# Schematic.net
KiCad netlist of a schematic drawn in EAGLE
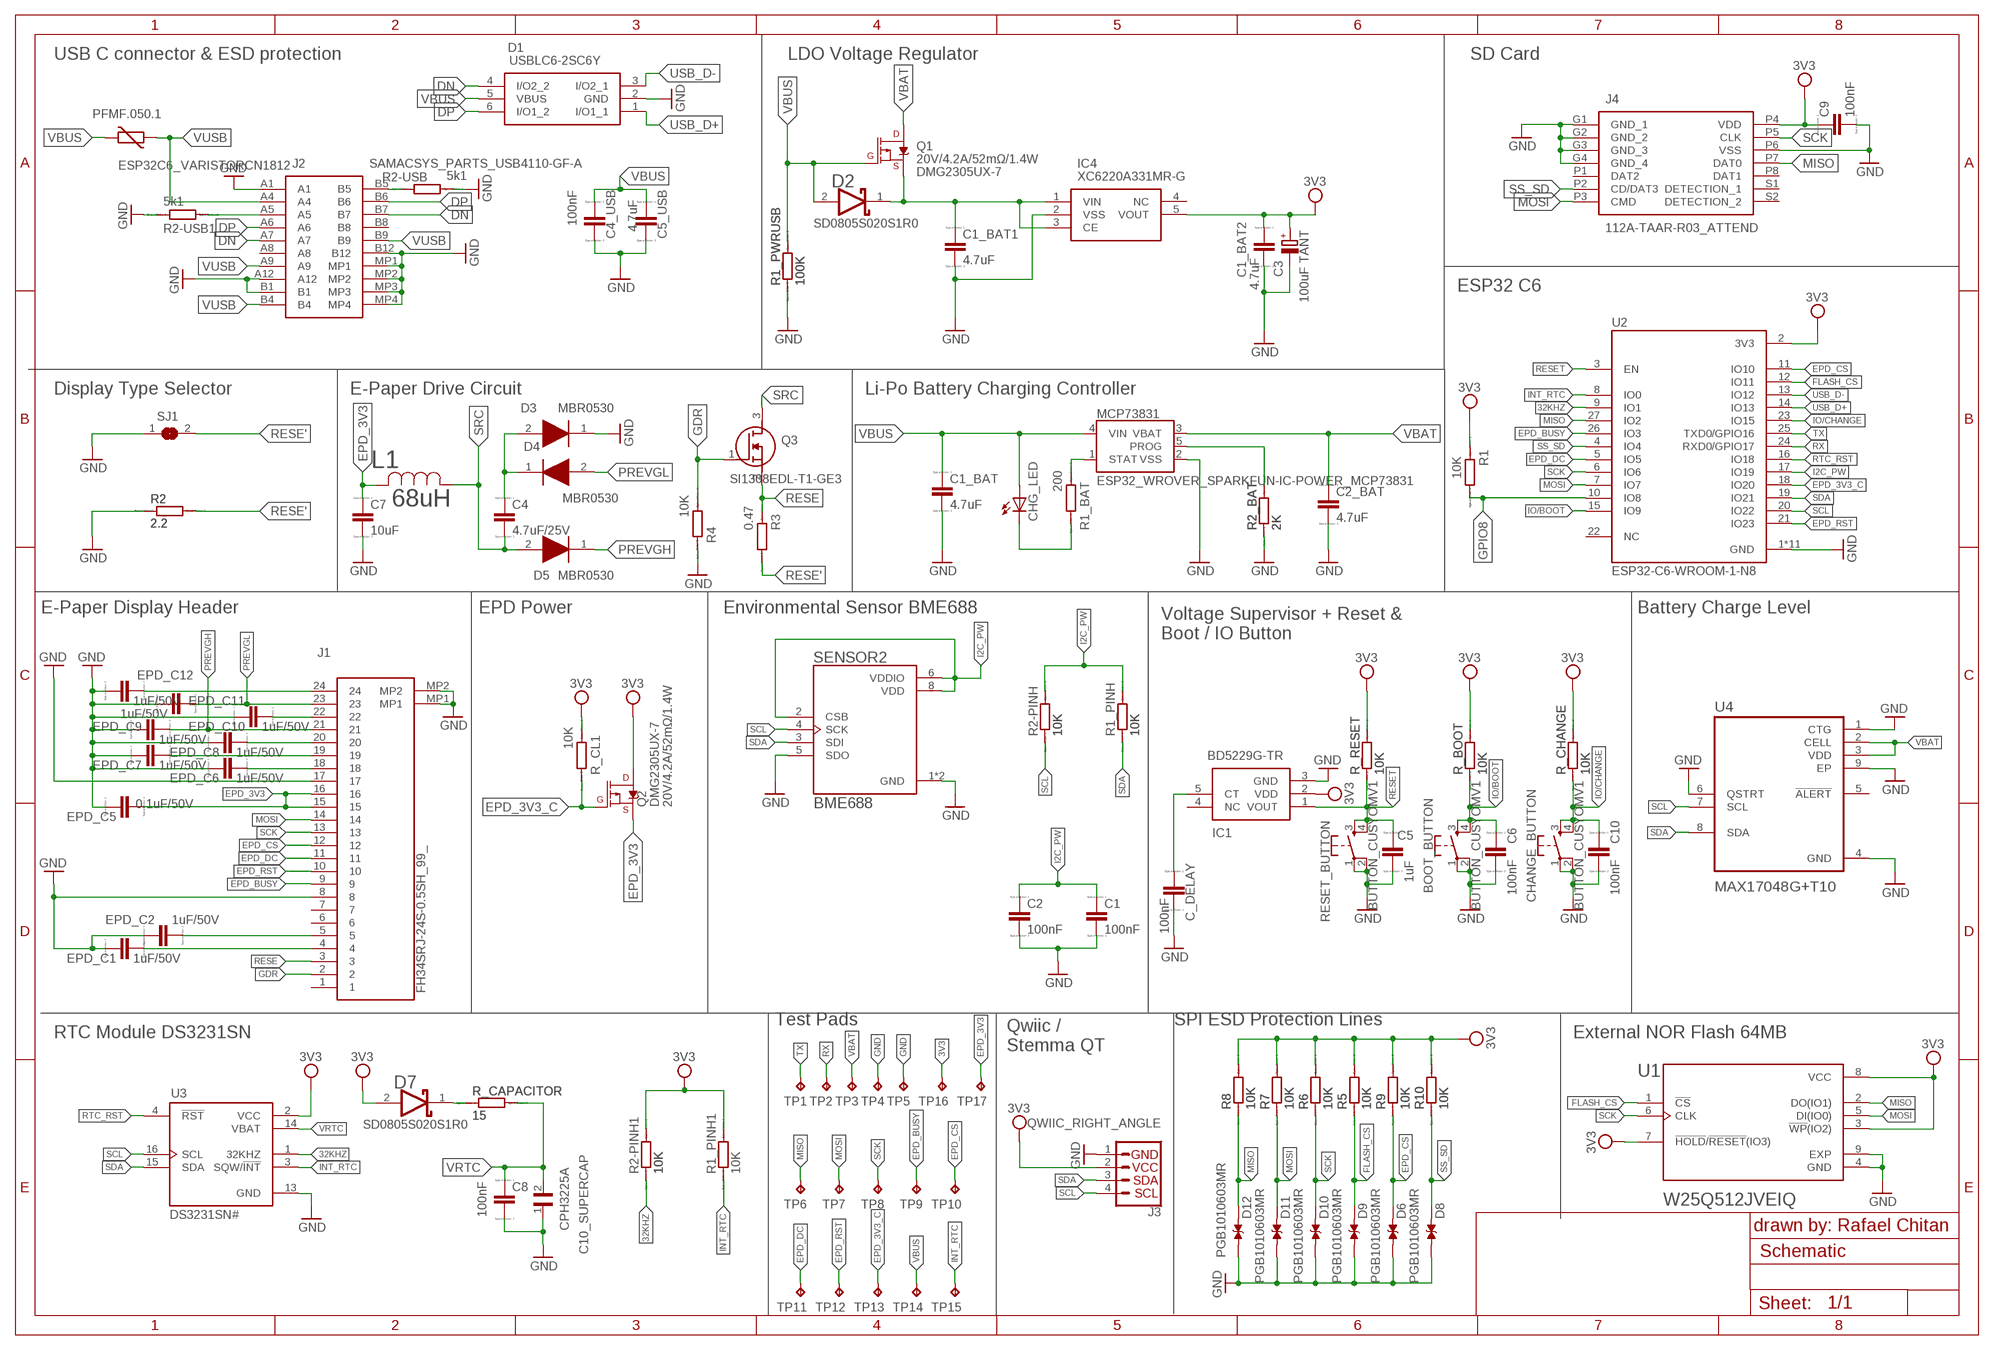
[diagram p0: schematic, sheet 1]

(export (version "E")
  (design (tool "Eeschema 10.0.6"))
  (components
    (comp (ref "BOOT_BUTTON")
      (value "BUTTON_CUSYOMV1")
      (footprint "eagle-import:MYBUTTON")
      (libsource (lib "eagle-import") (part "BUTTON_CUSYOMV1"))
    )
    (comp (ref "C1")
      (value "100nF")
      (footprint "eagle-import:EAGLE-LTSPICE_C0402")
      (libsource (lib "eagle-import") (part "EAGLE-LTSPICE_CC0402"))
    )
    (comp (ref "C1_BAT")
      (value "4.7uF")
      (footprint "eagle-import:EAGLE-LTSPICE_C0402")
      (libsource (lib "eagle-import") (part "EAGLE-LTSPICE_CC0402"))
    )
    (comp (ref "C1_BAT1")
      (value "4.7uF")
      (footprint "eagle-import:EAGLE-LTSPICE_C0402")
      (libsource (lib "eagle-import") (part "ESP32_WROVER_EAGLE-LTSPICE_CC0402"))
    )
    (comp (ref "C1_BAT2")
      (value "4.7uF")
      (footprint "eagle-import:EAGLE-LTSPICE_C0402")
      (libsource (lib "eagle-import") (part "ESP32_WROVER_EAGLE-LTSPICE_CC0402"))
    )
    (comp (ref "C2")
      (value "100nF")
      (footprint "eagle-import:EAGLE-LTSPICE_C0402")
      (libsource (lib "eagle-import") (part "EAGLE-LTSPICE_CC0402"))
    )
    (comp (ref "C2_BAT")
      (value "4.7uF")
      (footprint "eagle-import:EAGLE-LTSPICE_C0402")
      (libsource (lib "eagle-import") (part "EAGLE-LTSPICE_CC0402"))
    )
    (comp (ref "C3")
      (value "100uF TANT")
      (footprint "eagle-import:RCL_CT3528")
      (libsource (lib "eagle-import") (part "RCL_CPOL-EUCT3528"))
    )
    (comp (ref "C4")
      (value "4.7uF/25V")
      (footprint "eagle-import:EAGLE-LTSPICE_C0402")
      (libsource (lib "eagle-import") (part "EAGLE-LTSPICE_CC0402"))
    )
    (comp (ref "C4_USB")
      (value "100nF")
      (footprint "eagle-import:EAGLE-LTSPICE_C0402")
      (libsource (lib "eagle-import") (part "ESP32_WROVER_EAGLE-LTSPICE_CC0402"))
    )
    (comp (ref "C5")
      (value "1uF")
      (footprint "eagle-import:EAGLE-LTSPICE_C0402")
      (libsource (lib "eagle-import") (part "EAGLE-LTSPICE_CC0402"))
    )
    (comp (ref "C5_USB")
      (value "4.7uF")
      (footprint "eagle-import:EAGLE-LTSPICE_C0402")
      (libsource (lib "eagle-import") (part "ESP32_WROVER_EAGLE-LTSPICE_CC0402"))
    )
    (comp (ref "C6")
      (value "100nF")
      (footprint "eagle-import:EAGLE-LTSPICE_C0402")
      (libsource (lib "eagle-import") (part "EAGLE-LTSPICE_CC0402"))
    )
    (comp (ref "C7")
      (value "10uF")
      (footprint "eagle-import:EAGLE-LTSPICE_C0402")
      (libsource (lib "eagle-import") (part "EAGLE-LTSPICE_CC0402"))
    )
    (comp (ref "C8")
      (value "100nF")
      (footprint "eagle-import:EAGLE-LTSPICE_C0402")
      (libsource (lib "eagle-import") (part "EAGLE-LTSPICE_CC0402"))
    )
    (comp (ref "C9")
      (value "100nF")
      (footprint "eagle-import:EAGLE-LTSPICE_C0402")
      (libsource (lib "eagle-import") (part "EAGLE-LTSPICE_CC0402"))
    )
    (comp (ref "C10")
      (value "100nF")
      (footprint "eagle-import:EAGLE-LTSPICE_C0402")
      (libsource (lib "eagle-import") (part "EAGLE-LTSPICE_CC0402"))
    )
    (comp (ref "C10_SUPERCAP")
      (value "CPH3225A")
      (footprint "eagle-import:CAPCP3225X100N")
      (fields (field (name "MF") "Seiko Instruments"))
      (libsource (lib "eagle-import") (part "CPH3225A"))
    )
    (comp (ref "CHANGE_BUTTON")
      (value "BUTTON_CUSYOMV1")
      (footprint "eagle-import:MYBUTTON")
      (libsource (lib "eagle-import") (part "BUTTON_CUSYOMV1"))
    )
    (comp (ref "CHG_LED")
      (value "ADAFRUIT_LEDCHIP-LED0603")
      (footprint "eagle-import:ADAFRUIT_CHIP-LED0603")
      (libsource (lib "eagle-import") (part "ADAFRUIT_LEDCHIP-LED0603"))
    )
    (comp (ref "C_DELAY")
      (value "100nF")
      (footprint "eagle-import:EAGLE-LTSPICE_C0402")
      (libsource (lib "eagle-import") (part "EAGLE-LTSPICE_CC0402"))
    )
    (comp (ref "D1")
      (value "USBLC6-2SC6Y")
      (footprint "eagle-import:SOT95P280X145-6N")
      (fields (field (name "MF") "STMicroelectronics"))
      (libsource (lib "eagle-import") (part "USBLC6-2SC6Y"))
    )
    (comp (ref "D2")
      (value "ESP32_WROVER_AVX---SD0805S020S1R0_AVX_SD0805S020S1R0_0_0AVX_SD0805S020S1R0_0_0")
      (footprint "eagle-import:ESP32_WROVER_AVX---SD0805S020S1R0_AVX_SD0805S020S1R0_0")
      (fields
        (field (name "DIGIKEY_PART_NUMBER") "478-7800-1-ND")
        (field (name "MF") "AVX")
        (field (name "MOUSER_PART_NUMBER") "581-SD0805S020S1R0")
        (field (name "CODE") "SD0805S020S1R0")
      )
      (libsource (lib "eagle-import") (part "ESP32_WROVER_AVX---SD0805S020S1R0_AVX_SD0805S020S1R0_0_0AVX_SD0805S020S1R0_0_0"))
    )
    (comp (ref "D3")
      (value "MBR0530")
      (footprint "eagle-import:SOD3716X135N")
      (fields (field (name "MF") "ON Semiconductor"))
      (libsource (lib "eagle-import") (part "MBR0530"))
    )
    (comp (ref "D4")
      (value "MBR0530")
      (footprint "eagle-import:SOD3716X135N")
      (fields (field (name "MF") "ON Semiconductor"))
      (libsource (lib "eagle-import") (part "MBR0530"))
    )
    (comp (ref "D5")
      (value "MBR0530")
      (footprint "eagle-import:SOD3716X135N")
      (fields (field (name "MF") "ON Semiconductor"))
      (libsource (lib "eagle-import") (part "MBR0530"))
    )
    (comp (ref "D6")
      (value "PGB1010603MR")
      (footprint "eagle-import:DIOC1608X36N")
      (fields (field (name "MF") "Littelfuse Inc."))
      (libsource (lib "eagle-import") (part "PGB1010603MR"))
    )
    (comp (ref "D7")
      (value "ESP32_WROVER_AVX---SD0805S020S1R0_AVX_SD0805S020S1R0_0_0AVX_SD0805S020S1R0_0_0")
      (footprint "eagle-import:ESP32_WROVER_AVX---SD0805S020S1R0_AVX_SD0805S020S1R0_0")
      (fields
        (field (name "DIGIKEY_PART_NUMBER") "478-7800-1-ND")
        (field (name "MF") "AVX")
        (field (name "MOUSER_PART_NUMBER") "581-SD0805S020S1R0")
        (field (name "CODE") "SD0805S020S1R0")
      )
      (libsource (lib "eagle-import") (part "ESP32_WROVER_AVX---SD0805S020S1R0_AVX_SD0805S020S1R0_0_0AVX_SD0805S020S1R0_0_0"))
    )
    (comp (ref "D8")
      (value "PGB1010603MR")
      (footprint "eagle-import:DIOC1608X36N")
      (fields (field (name "MF") "Littelfuse Inc."))
      (libsource (lib "eagle-import") (part "PGB1010603MR"))
    )
    (comp (ref "D9")
      (value "PGB1010603MR")
      (footprint "eagle-import:DIOC1608X36N")
      (fields (field (name "MF") "Littelfuse Inc."))
      (libsource (lib "eagle-import") (part "PGB1010603MR"))
    )
    (comp (ref "D10")
      (value "PGB1010603MR")
      (footprint "eagle-import:DIOC1608X36N")
      (fields (field (name "MF") "Littelfuse Inc."))
      (libsource (lib "eagle-import") (part "PGB1010603MR"))
    )
    (comp (ref "D11")
      (value "PGB1010603MR")
      (footprint "eagle-import:DIOC1608X36N")
      (fields (field (name "MF") "Littelfuse Inc."))
      (libsource (lib "eagle-import") (part "PGB1010603MR"))
    )
    (comp (ref "D12")
      (value "PGB1010603MR")
      (footprint "eagle-import:DIOC1608X36N")
      (fields (field (name "MF") "Littelfuse Inc."))
      (libsource (lib "eagle-import") (part "PGB1010603MR"))
    )
    (comp (ref "EPD_C1")
      (value "1uF/50V")
      (footprint "eagle-import:EAGLE-LTSPICE_C0402")
      (libsource (lib "eagle-import") (part "EAGLE-LTSPICE_CC0402"))
    )
    (comp (ref "EPD_C2")
      (value "1uF/50V")
      (footprint "eagle-import:EAGLE-LTSPICE_C0402")
      (libsource (lib "eagle-import") (part "EAGLE-LTSPICE_CC0402"))
    )
    (comp (ref "EPD_C5")
      (value "0.1uF/50V")
      (footprint "eagle-import:EAGLE-LTSPICE_C0402")
      (libsource (lib "eagle-import") (part "EAGLE-LTSPICE_CC0402"))
    )
    (comp (ref "EPD_C6")
      (value "1uF/50V")
      (footprint "eagle-import:EAGLE-LTSPICE_C0402")
      (libsource (lib "eagle-import") (part "EAGLE-LTSPICE_CC0402"))
    )
    (comp (ref "EPD_C7")
      (value "1uF/50V")
      (footprint "eagle-import:EAGLE-LTSPICE_C0402")
      (libsource (lib "eagle-import") (part "EAGLE-LTSPICE_CC0402"))
    )
    (comp (ref "EPD_C8")
      (value "1uF/50V")
      (footprint "eagle-import:EAGLE-LTSPICE_C0402")
      (libsource (lib "eagle-import") (part "EAGLE-LTSPICE_CC0402"))
    )
    (comp (ref "EPD_C9")
      (value "1uF/50V")
      (footprint "eagle-import:EAGLE-LTSPICE_C0402")
      (libsource (lib "eagle-import") (part "EAGLE-LTSPICE_CC0402"))
    )
    (comp (ref "EPD_C10")
      (value "1uF/50V")
      (footprint "eagle-import:EAGLE-LTSPICE_C0402")
      (libsource (lib "eagle-import") (part "EAGLE-LTSPICE_CC0402"))
    )
    (comp (ref "EPD_C11")
      (value "1uF/50V")
      (footprint "eagle-import:EAGLE-LTSPICE_C0402")
      (libsource (lib "eagle-import") (part "EAGLE-LTSPICE_CC0402"))
    )
    (comp (ref "EPD_C12")
      (value "1uF/50V")
      (footprint "eagle-import:EAGLE-LTSPICE_C0402")
      (libsource (lib "eagle-import") (part "EAGLE-LTSPICE_CC0402"))
    )
    (comp (ref "IC1")
      (value "BD5229G-TR")
      (footprint "eagle-import:SOT95P280X125-5N")
      (fields (field (name "MOUSER_PART_NUMBER") "755-BD5229G-TR"))
      (libsource (lib "eagle-import") (part "BD5229G-TR"))
    )
    (comp (ref "IC4")
      (value "XC6220A331MR-G")
      (footprint "eagle-import:SOT95P280X120-5N")
      (fields (field (name "MOUSER_PART_NUMBER") "865-XC6220A331MR-G"))
      (libsource (lib "eagle-import") (part "XC6220A331MR-G"))
    )
    (comp (ref "J1")
      (value "FH34SRJ-24S-0.5SH_99_")
      (footprint "eagle-import:FH34SRJ24S05SH99")
      (fields
        (field (name "MANUFACTURER_PART_NUMBER") "FH34SRJ-24S-0.5SH(99)")
        (field (name "MOUSER_PART_NUMBER") "798-FH34SRJ24S05SH99")
      )
      (libsource (lib "eagle-import") (part "FH34SRJ-24S-0.5SH_99_"))
    )
    (comp (ref "J2")
      (value "SAMACSYS_PARTS_USB4110-GF-A")
      (footprint "eagle-import:SAMACSYS_PARTS_USB4110GFA")
      (fields
        (field (name "MANUFACTURER_PART_NUMBER") "USB4110-GF-A")
        (field (name "MOUSER_PART_NUMBER") "640-USB4110-GF-A")
      )
      (libsource (lib "eagle-import") (part "SAMACSYS_PARTS_USB4110-GF-A"))
    )
    (comp (ref "J3")
      (value "QWIIC_RIGHT_ANGLE")
      (footprint "eagle-import:JST04_1MM_RA")
      (libsource (lib "eagle-import") (part "QWIIC_CONNECTORJS-1MM"))
    )
    (comp (ref "J4")
      (value "112A-TAAR-R03_ATTEND")
      (footprint "eagle-import:112ATAARR03ATTEND")
      (fields (field (name "MANUFACTURER_PART_NUMBER") "112A-TAAR-R03 ATTEND"))
      (libsource (lib "eagle-import") (part "112A-TAAR-R03_ATTEND"))
    )
    (comp (ref "L1")
      (value "68uH")
      (footprint "eagle-import:IND_4828-WE-TPC_WRE")
      (fields
        (field (name "MANUFACTURER_PART_NUMBER") "744043680")
        (field (name "COPYRIGHT") "Copyright (C) 2024 Ultra Librarian. All rights reserved.")
      )
      (libsource (lib "eagle-import") (part "744043680IND_4828-WE-TPC_WRE"))
    )
    (comp (ref "MCP73831")
      (value "ESP32_WROVER_SPARKFUN-IC-POWER_MCP73831")
      (footprint "eagle-import:ESP32_WROVER_SPARKFUN-IC-POWER_SOT23-5")
      (libsource (lib "eagle-import") (part "ESP32_WROVER_SPARKFUN-IC-POWER_MCP73831"))
    )
    (comp (ref "PFMF.050.1")
      (value "ESP32C6_VARISTORCN1812")
      (footprint "eagle-import:ESP32C6_VARISTOR_CT_CN1812")
      (libsource (lib "eagle-import") (part "ESP32C6_VARISTORCN1812"))
    )
    (comp (ref "Q1")
      (value "20V/4.2A/52mΩ/1.4W")
      (footprint "eagle-import:ESP32_WROVER_SPARKFUN-DISCRETESEMI_SOT23-3")
      (fields (field (name "CODE") "DMG2305UX-7"))
      (libsource (lib "eagle-import") (part "ESP32_WROVER_SPARKFUN-DISCRETESEMI_MOSFET_PCH-DMG2305UX-7"))
    )
    (comp (ref "Q2")
      (value "20V/4.2A/52mΩ/1.4W")
      (footprint "eagle-import:ESP32_WROVER_SPARKFUN-DISCRETESEMI_SOT23-3")
      (fields (field (name "CODE") "DMG2305UX-7"))
      (libsource (lib "eagle-import") (part "ESP32_WROVER_SPARKFUN-DISCRETESEMI_MOSFET_PCH-DMG2305UX-7"))
    )
    (comp (ref "Q3")
      (value "SI1308EDL-T1-GE3")
      (footprint "eagle-import:SOT65P210X110-3N")
      (fields (field (name "MF") "Vishay Siliconix"))
      (libsource (lib "eagle-import") (part "SI1308EDL-T1-GE3"))
    )
    (comp (ref "R1")
      (value "10K")
      (footprint "eagle-import:ESP32_WROVER_EAGLE-LTSPICE_R0402")
      (libsource (lib "eagle-import") (part "ESP32_WROVER_EAGLE-LTSPICE_RR0402"))
    )
    (comp (ref "R1_BAT")
      (value "200")
      (footprint "eagle-import:ESP32_WROVER_EAGLE-LTSPICE_R0402")
      (libsource (lib "eagle-import") (part "ESP32_WROVER_EAGLE-LTSPICE_RR0402"))
    )
    (comp (ref "R1_PINH")
      (value "10K")
      (footprint "eagle-import:ESP32_WROVER_EAGLE-LTSPICE_R0402")
      (libsource (lib "eagle-import") (part "ESP32_WROVER_EAGLE-LTSPICE_RR0402"))
    )
    (comp (ref "R1_PINH1")
      (value "10K")
      (footprint "eagle-import:ESP32_WROVER_EAGLE-LTSPICE_R0402")
      (libsource (lib "eagle-import") (part "ESP32_WROVER_EAGLE-LTSPICE_RR0402"))
    )
    (comp (ref "R1_PWRUSB")
      (value "100K")
      (footprint "eagle-import:ESP32_WROVER_EAGLE-LTSPICE_R0402")
      (libsource (lib "eagle-import") (part "ESP32_WROVER_EAGLE-LTSPICE_RR0402"))
    )
    (comp (ref "R2")
      (value "2.2")
      (footprint "eagle-import:ESP32_WROVER_EAGLE-LTSPICE_R0402")
      (libsource (lib "eagle-import") (part "ESP32_WROVER_EAGLE-LTSPICE_RR0402"))
    )
    (comp (ref "R2-PINH")
      (value "10K")
      (footprint "eagle-import:ESP32_WROVER_EAGLE-LTSPICE_R0402")
      (libsource (lib "eagle-import") (part "ESP32_WROVER_EAGLE-LTSPICE_RR0402"))
    )
    (comp (ref "R2-PINH1")
      (value "10K")
      (footprint "eagle-import:ESP32_WROVER_EAGLE-LTSPICE_R0402")
      (libsource (lib "eagle-import") (part "ESP32_WROVER_EAGLE-LTSPICE_RR0402"))
    )
    (comp (ref "R2-USB")
      (value "5k1")
      (footprint "eagle-import:ESP32_WROVER_EAGLE-LTSPICE_R0402")
      (libsource (lib "eagle-import") (part "ESP32_WROVER_EAGLE-LTSPICE_RR0402"))
    )
    (comp (ref "R2-USB1")
      (value "5k1")
      (footprint "eagle-import:ESP32_WROVER_EAGLE-LTSPICE_R0402")
      (libsource (lib "eagle-import") (part "ESP32_WROVER_EAGLE-LTSPICE_RR0402"))
    )
    (comp (ref "R2_BAT")
      (value "2K")
      (footprint "eagle-import:ESP32_WROVER_EAGLE-LTSPICE_R0402")
      (libsource (lib "eagle-import") (part "ESP32_WROVER_EAGLE-LTSPICE_RR0402"))
    )
    (comp (ref "R3")
      (value "0.47")
      (footprint "eagle-import:ESP32_WROVER_EAGLE-LTSPICE_R0402")
      (libsource (lib "eagle-import") (part "ESP32_WROVER_EAGLE-LTSPICE_RR0402"))
    )
    (comp (ref "R4")
      (value "10K")
      (footprint "eagle-import:ESP32_WROVER_EAGLE-LTSPICE_R0402")
      (libsource (lib "eagle-import") (part "ESP32_WROVER_EAGLE-LTSPICE_RR0402"))
    )
    (comp (ref "R5")
      (value "10K")
      (footprint "eagle-import:ESP32_WROVER_EAGLE-LTSPICE_R0402")
      (libsource (lib "eagle-import") (part "ESP32_WROVER_EAGLE-LTSPICE_RR0402"))
    )
    (comp (ref "R6")
      (value "10K")
      (footprint "eagle-import:ESP32_WROVER_EAGLE-LTSPICE_R0402")
      (libsource (lib "eagle-import") (part "ESP32_WROVER_EAGLE-LTSPICE_RR0402"))
    )
    (comp (ref "R7")
      (value "10K")
      (footprint "eagle-import:ESP32_WROVER_EAGLE-LTSPICE_R0402")
      (libsource (lib "eagle-import") (part "ESP32_WROVER_EAGLE-LTSPICE_RR0402"))
    )
    (comp (ref "R8")
      (value "10K")
      (footprint "eagle-import:ESP32_WROVER_EAGLE-LTSPICE_R0402")
      (libsource (lib "eagle-import") (part "ESP32_WROVER_EAGLE-LTSPICE_RR0402"))
    )
    (comp (ref "R9")
      (value "10K")
      (footprint "eagle-import:ESP32_WROVER_EAGLE-LTSPICE_R0402")
      (libsource (lib "eagle-import") (part "ESP32_WROVER_EAGLE-LTSPICE_RR0402"))
    )
    (comp (ref "R10")
      (value "10K")
      (footprint "eagle-import:ESP32_WROVER_EAGLE-LTSPICE_R0402")
      (libsource (lib "eagle-import") (part "ESP32_WROVER_EAGLE-LTSPICE_RR0402"))
    )
    (comp (ref "RESET_BUTTON")
      (value "BUTTON_CUSYOMV1")
      (footprint "eagle-import:MYBUTTON")
      (libsource (lib "eagle-import") (part "BUTTON_CUSYOMV1"))
    )
    (comp (ref "R_BOOT")
      (value "10K")
      (footprint "eagle-import:ESP32_WROVER_EAGLE-LTSPICE_R0402")
      (libsource (lib "eagle-import") (part "ESP32_WROVER_EAGLE-LTSPICE_RR0402"))
    )
    (comp (ref "R_CAPACITOR")
      (value "15")
      (footprint "eagle-import:ESP32_WROVER_EAGLE-LTSPICE_R0402")
      (libsource (lib "eagle-import") (part "ESP32_WROVER_EAGLE-LTSPICE_RR0402"))
    )
    (comp (ref "R_CHANGE")
      (value "10K")
      (footprint "eagle-import:ESP32_WROVER_EAGLE-LTSPICE_R0402")
      (libsource (lib "eagle-import") (part "ESP32_WROVER_EAGLE-LTSPICE_RR0402"))
    )
    (comp (ref "R_CL1")
      (value "10K")
      (footprint "eagle-import:ESP32_WROVER_EAGLE-LTSPICE_R0402")
      (libsource (lib "eagle-import") (part "ESP32_WROVER_EAGLE-LTSPICE_RR0402"))
    )
    (comp (ref "R_RESET")
      (value "10K")
      (footprint "eagle-import:ESP32_WROVER_EAGLE-LTSPICE_R0402")
      (libsource (lib "eagle-import") (part "ESP32_WROVER_EAGLE-LTSPICE_RR0402"))
    )
    (comp (ref "SENSOR2")
      (value "BME688")
      (footprint "eagle-import:ESP32_WROVER_BME680_PSON80P300X300X100-8N")
      (fields (field (name "MF") "Bosch Sensortec") (field (name "MP") "BME680"))
      (libsource (lib "eagle-import") (part "ESP32_WROVER_BME680_BME680"))
    )
    (comp (ref "SJ1") (value "SJ") (footprint "eagle-import:SJ") (libsource (lib "eagle-import") (part "SJ")))
    (comp (ref "TP1")
      (value "TPTP20R")
      (footprint "eagle-import:TP20R")
      (libsource (lib "eagle-import") (part "TPTP20R"))
    )
    (comp (ref "TP2")
      (value "TPTP20R")
      (footprint "eagle-import:TP20R")
      (libsource (lib "eagle-import") (part "TPTP20R"))
    )
    (comp (ref "TP3")
      (value "TPTP20R")
      (footprint "eagle-import:TP20R")
      (libsource (lib "eagle-import") (part "TPTP20R"))
    )
    (comp (ref "TP4")
      (value "TPTP20R")
      (footprint "eagle-import:TP20R")
      (libsource (lib "eagle-import") (part "TPTP20R"))
    )
    (comp (ref "TP5")
      (value "TPTP20R")
      (footprint "eagle-import:TP20R")
      (libsource (lib "eagle-import") (part "TPTP20R"))
    )
    (comp (ref "TP6")
      (value "TPTP20R")
      (footprint "eagle-import:TP20R")
      (libsource (lib "eagle-import") (part "TPTP20R"))
    )
    (comp (ref "TP7")
      (value "TPTP20R")
      (footprint "eagle-import:TP20R")
      (libsource (lib "eagle-import") (part "TPTP20R"))
    )
    (comp (ref "TP8")
      (value "TPTP20R")
      (footprint "eagle-import:TP20R")
      (libsource (lib "eagle-import") (part "TPTP20R"))
    )
    (comp (ref "TP9")
      (value "TPTP20R")
      (footprint "eagle-import:TP20R")
      (libsource (lib "eagle-import") (part "TPTP20R"))
    )
    (comp (ref "TP10")
      (value "TPTP20R")
      (footprint "eagle-import:TP20R")
      (libsource (lib "eagle-import") (part "TPTP20R"))
    )
    (comp (ref "TP11")
      (value "TPTP20R")
      (footprint "eagle-import:TP20R")
      (libsource (lib "eagle-import") (part "TPTP20R"))
    )
    (comp (ref "TP12")
      (value "TPTP20R")
      (footprint "eagle-import:TP20R")
      (libsource (lib "eagle-import") (part "TPTP20R"))
    )
    (comp (ref "TP13")
      (value "TPTP20R")
      (footprint "eagle-import:TP20R")
      (libsource (lib "eagle-import") (part "TPTP20R"))
    )
    (comp (ref "TP14")
      (value "TPTP20R")
      (footprint "eagle-import:TP20R")
      (libsource (lib "eagle-import") (part "TPTP20R"))
    )
    (comp (ref "TP15")
      (value "TPTP20R")
      (footprint "eagle-import:TP20R")
      (libsource (lib "eagle-import") (part "TPTP20R"))
    )
    (comp (ref "TP16")
      (value "TPTP20R")
      (footprint "eagle-import:TP20R")
      (libsource (lib "eagle-import") (part "TPTP20R"))
    )
    (comp (ref "TP17")
      (value "TPTP20R")
      (footprint "eagle-import:TP20R")
      (libsource (lib "eagle-import") (part "TPTP20R"))
    )
    (comp (ref "U1")
      (value "W25Q512JVEIQ")
      (footprint "eagle-import:SON127P600X800X80-9N")
      (fields (field (name "MF") "Winbond Electronics"))
      (libsource (lib "eagle-import") (part "W25Q512JVEIQ"))
    )
    (comp (ref "U2")
      (value "ESP32-C6-WROOM-1-N8")
      (footprint "eagle-import:XCVR_ESP32-C6-WROOM-1-N8")
      (fields (field (name "MF") "Espressif Systems"))
      (libsource (lib "eagle-import") (part "ESP32-C6-WROOM-1-N8"))
    )
    (comp (ref "U3")
      (value "DS3231SN#")
      (footprint "eagle-import:SOIC127P1032X265-16N")
      (fields (field (name "MF") "Analog Devices"))
      (libsource (lib "eagle-import") (part "DS3231SN#"))
    )
    (comp (ref "U4")
      (value "MAX17048G+T10")
      (footprint "eagle-import:SON50P200X200X80-9N")
      (fields (field (name "MF") "Analog Devices"))
      (libsource (lib "eagle-import") (part "MAX17048G+T10"))
    )
  )
  (nets
    (net (code "1") (name "3V3") (class "Default")
      (node (ref "C1_BAT2") (pin "1") (pinfunction "1_1") (pintype "passive"))
      (node (ref "C3") (pin "+") (pinfunction "+_+") (pintype "passive"))
      (node (ref "C9") (pin "1") (pinfunction "1_1") (pintype "passive"))
      (node (ref "D7") (pin "2") (pinfunction "ANODE_2") (pintype "bidirectional"))
      (node (ref "IC1") (pin "2") (pinfunction "VDD_2") (pintype "bidirectional"))
      (node (ref "IC4") (pin "5") (pinfunction "VOUT_5") (pintype "bidirectional"))
      (node (ref "J3") (pin "2") (pinfunction "2_2") (pintype "power_in"))
      (node (ref "J4") (pin "P4") (pinfunction "VDD_P4") (pintype "bidirectional"))
      (node (ref "Q2") (pin "3") (pinfunction "D_3") (pintype "bidirectional"))
      (node (ref "R1") (pin "2") (pinfunction "2_2") (pintype "passive"))
      (node (ref "R10") (pin "2") (pinfunction "2_2") (pintype "passive"))
      (node (ref "R1_PINH1") (pin "2") (pinfunction "2_2") (pintype "passive"))
      (node (ref "R2-PINH1") (pin "2") (pinfunction "2_2") (pintype "passive"))
      (node (ref "R5") (pin "2") (pinfunction "2_2") (pintype "passive"))
      (node (ref "R6") (pin "2") (pinfunction "2_2") (pintype "passive"))
      (node (ref "R7") (pin "2") (pinfunction "2_2") (pintype "passive"))
      (node (ref "R8") (pin "2") (pinfunction "2_2") (pintype "passive"))
      (node (ref "R9") (pin "2") (pinfunction "2_2") (pintype "passive"))
      (node (ref "R_BOOT") (pin "2") (pinfunction "2_2") (pintype "passive"))
      (node (ref "R_CHANGE") (pin "2") (pinfunction "2_2") (pintype "passive"))
      (node (ref "R_CL1") (pin "2") (pinfunction "2_2") (pintype "passive"))
      (node (ref "R_RESET") (pin "2") (pinfunction "2_2") (pintype "passive"))
      (node (ref "TP16") (pin "TP") (pinfunction "TP_TP") (pintype "input"))
      (node (ref "U1") (pin "3") (pinfunction "~{WP}(IO2)_3") (pintype "bidirectional"))
      (node (ref "U1") (pin "7") (pinfunction "~{HOLD}/~{RESET}(IO3)_7") (pintype "bidirectional"))
      (node (ref "U1") (pin "8") (pinfunction "VCC_8") (pintype "power_in"))
      (node (ref "U2") (pin "2") (pinfunction "3V3_2") (pintype "power_in"))
      (node (ref "U3") (pin "2") (pinfunction "VCC_2") (pintype "power_in"))
    )
    (net (code "2") (name "32KHZ") (class "Default")
      (node (ref "R2-PINH1") (pin "1") (pinfunction "1_1") (pintype "passive"))
      (node (ref "U2") (pin "9") (pinfunction "IO1_9") (pintype "bidirectional"))
      (node (ref "U3") (pin "1") (pinfunction "32KHZ_1") (pintype "output"))
    )
    (net (code "3") (name "DN") (class "Default")
      (node (ref "D1") (pin "4") (pinfunction "I/O2_2_4") (pintype "bidirectional"))
      (node (ref "J2") (pin "A7") (pinfunction "A7_A7") (pintype "bidirectional"))
      (node (ref "J2") (pin "B7") (pinfunction "B7_B7") (pintype "bidirectional"))
    )
    (net (code "4") (name "DP") (class "Default")
      (node (ref "D1") (pin "6") (pinfunction "I/O1_2_6") (pintype "bidirectional"))
      (node (ref "J2") (pin "A6") (pinfunction "A6_A6") (pintype "bidirectional"))
      (node (ref "J2") (pin "B6") (pinfunction "B6_B6") (pintype "bidirectional"))
    )
    (net (code "5") (name "EPD_3V3") (class "Default")
      (node (ref "C7") (pin "1") (pinfunction "1_1") (pintype "passive"))
      (node (ref "EPD_C5") (pin "2") (pinfunction "2_2") (pintype "passive"))
      (node (ref "J1") (pin "15") (pinfunction "15_15") (pintype "bidirectional"))
      (node (ref "J1") (pin "16") (pinfunction "16_16") (pintype "bidirectional"))
      (node (ref "L1") (pin "2") (pinfunction "2_2") (pintype "passive"))
      (node (ref "Q2") (pin "2") (pinfunction "S_2") (pintype "bidirectional"))
      (node (ref "TP17") (pin "TP") (pinfunction "TP_TP") (pintype "input"))
    )
    (net (code "6") (name "EPD_3V3_C") (class "Default")
      (node (ref "Q2") (pin "1") (pinfunction "G_1") (pintype "bidirectional"))
      (node (ref "R_CL1") (pin "1") (pinfunction "1_1") (pintype "passive"))
      (node (ref "TP13") (pin "TP") (pinfunction "TP_TP") (pintype "input"))
      (node (ref "U2") (pin "18") (pinfunction "IO20_18") (pintype "bidirectional"))
    )
    (net (code "7") (name "EPD_BUSY") (class "Default")
      (node (ref "J1") (pin "9") (pinfunction "9_9") (pintype "bidirectional"))
      (node (ref "TP9") (pin "TP") (pinfunction "TP_TP") (pintype "input"))
      (node (ref "U2") (pin "26") (pinfunction "IO3_26") (pintype "bidirectional"))
    )
    (net (code "8") (name "EPD_CS") (class "Default")
      (node (ref "D6") (pin "2") (pinfunction "2_2") (pintype "passive"))
      (node (ref "J1") (pin "12") (pinfunction "12_12") (pintype "bidirectional"))
      (node (ref "R9") (pin "1") (pinfunction "1_1") (pintype "passive"))
      (node (ref "TP10") (pin "TP") (pinfunction "TP_TP") (pintype "input"))
      (node (ref "U2") (pin "11") (pinfunction "IO10_11") (pintype "bidirectional"))
    )
    (net (code "9") (name "EPD_DC") (class "Default")
      (node (ref "J1") (pin "11") (pinfunction "11_11") (pintype "bidirectional"))
      (node (ref "TP11") (pin "TP") (pinfunction "TP_TP") (pintype "input"))
      (node (ref "U2") (pin "5") (pinfunction "IO5_5") (pintype "bidirectional"))
    )
    (net (code "10") (name "EPD_RST") (class "Default")
      (node (ref "J1") (pin "10") (pinfunction "10_10") (pintype "bidirectional"))
      (node (ref "TP12") (pin "TP") (pinfunction "TP_TP") (pintype "input"))
      (node (ref "U2") (pin "21") (pinfunction "IO23_21") (pintype "bidirectional"))
    )
    (net (code "11") (name "FLASH_CS") (class "Default")
      (node (ref "D9") (pin "2") (pinfunction "2_2") (pintype "passive"))
      (node (ref "R5") (pin "1") (pinfunction "1_1") (pintype "passive"))
      (node (ref "U1") (pin "1") (pinfunction "~{CS}_1") (pintype "input"))
      (node (ref "U2") (pin "12") (pinfunction "IO11_12") (pintype "bidirectional"))
    )
    (net (code "12") (name "GDR") (class "Default")
      (node (ref "J1") (pin "2") (pinfunction "2_2") (pintype "bidirectional"))
      (node (ref "Q3") (pin "1") (pinfunction "G_1") (pintype "bidirectional"))
      (node (ref "R4") (pin "2") (pinfunction "2_2") (pintype "passive"))
    )
    (net (code "13") (name "GND") (class "Default")
      (node (ref "BOOT_BUTTON") (pin "1") (pinfunction "1_1") (pintype "passive"))
      (node (ref "BOOT_BUTTON") (pin "2") (pinfunction "2_2") (pintype "passive"))
      (node (ref "C1") (pin "2") (pinfunction "2_2") (pintype "passive"))
      (node (ref "C10") (pin "2") (pinfunction "2_2") (pintype "passive"))
      (node (ref "C10_SUPERCAP") (pin "1") (pinfunction "1_1") (pintype "passive"))
      (node (ref "C1_BAT") (pin "2") (pinfunction "2_2") (pintype "passive"))
      (node (ref "C1_BAT1") (pin "2") (pinfunction "2_2") (pintype "passive"))
      (node (ref "C1_BAT2") (pin "2") (pinfunction "2_2") (pintype "passive"))
      (node (ref "C2") (pin "2") (pinfunction "2_2") (pintype "passive"))
      (node (ref "C2_BAT") (pin "2") (pinfunction "2_2") (pintype "passive"))
      (node (ref "C3") (pin "-") (pinfunction "-_-") (pintype "passive"))
      (node (ref "C4_USB") (pin "2") (pinfunction "2_2") (pintype "passive"))
      (node (ref "C5") (pin "2") (pinfunction "2_2") (pintype "passive"))
      (node (ref "C5_USB") (pin "2") (pinfunction "2_2") (pintype "passive"))
      (node (ref "C6") (pin "2") (pinfunction "2_2") (pintype "passive"))
      (node (ref "C7") (pin "2") (pinfunction "2_2") (pintype "passive"))
      (node (ref "C8") (pin "2") (pinfunction "2_2") (pintype "passive"))
      (node (ref "C9") (pin "2") (pinfunction "2_2") (pintype "passive"))
      (node (ref "CHANGE_BUTTON") (pin "1") (pinfunction "1_1") (pintype "passive"))
      (node (ref "CHANGE_BUTTON") (pin "2") (pinfunction "2_2") (pintype "passive"))
      (node (ref "C_DELAY") (pin "2") (pinfunction "2_2") (pintype "passive"))
      (node (ref "D1") (pin "2") (pinfunction "GND_2") (pintype "bidirectional"))
      (node (ref "D10") (pin "1") (pinfunction "1_1") (pintype "passive"))
      (node (ref "D11") (pin "1") (pinfunction "1_1") (pintype "passive"))
      (node (ref "D12") (pin "1") (pinfunction "1_1") (pintype "passive"))
      (node (ref "D3") (pin "1") (pinfunction "K_1") (pintype "bidirectional"))
      (node (ref "D6") (pin "1") (pinfunction "1_1") (pintype "passive"))
      (node (ref "D8") (pin "1") (pinfunction "1_1") (pintype "passive"))
      (node (ref "D9") (pin "1") (pinfunction "1_1") (pintype "passive"))
      (node (ref "EPD_C1") (pin "1") (pinfunction "1_1") (pintype "passive"))
      (node (ref "EPD_C10") (pin "1") (pinfunction "1_1") (pintype "passive"))
      (node (ref "EPD_C11") (pin "1") (pinfunction "1_1") (pintype "passive"))
      (node (ref "EPD_C12") (pin "1") (pinfunction "1_1") (pintype "passive"))
      (node (ref "EPD_C2") (pin "1") (pinfunction "1_1") (pintype "passive"))
      (node (ref "EPD_C5") (pin "1") (pinfunction "1_1") (pintype "passive"))
      (node (ref "EPD_C6") (pin "1") (pinfunction "1_1") (pintype "passive"))
      (node (ref "EPD_C7") (pin "1") (pinfunction "1_1") (pintype "passive"))
      (node (ref "EPD_C8") (pin "1") (pinfunction "1_1") (pintype "passive"))
      (node (ref "EPD_C9") (pin "1") (pinfunction "1_1") (pintype "passive"))
      (node (ref "IC1") (pin "3") (pinfunction "GND_3") (pintype "bidirectional"))
      (node (ref "IC4") (pin "2") (pinfunction "VSS_2") (pintype "bidirectional"))
      (node (ref "J1") (pin "17") (pinfunction "17_17") (pintype "bidirectional"))
      (node (ref "J1") (pin "8") (pinfunction "8_8") (pintype "bidirectional"))
      (node (ref "J1") (pin "MP1") (pinfunction "MP1_MP1") (pintype "bidirectional"))
      (node (ref "J1") (pin "MP2") (pinfunction "MP2_MP2") (pintype "bidirectional"))
      (node (ref "J2") (pin "A1") (pinfunction "A1_A1") (pintype "bidirectional"))
      (node (ref "J2") (pin "A12") (pinfunction "A12_A12") (pintype "bidirectional"))
      (node (ref "J2") (pin "B1") (pinfunction "B1_B1") (pintype "bidirectional"))
      (node (ref "J2") (pin "B12") (pinfunction "B12_B12") (pintype "bidirectional"))
      (node (ref "J2") (pin "MP1") (pinfunction "MP1_MP1") (pintype "bidirectional"))
      (node (ref "J2") (pin "MP2") (pinfunction "MP2_MP2") (pintype "bidirectional"))
      (node (ref "J2") (pin "MP3") (pinfunction "MP3_MP3") (pintype "bidirectional"))
      (node (ref "J2") (pin "MP4") (pinfunction "MP4_MP4") (pintype "bidirectional"))
      (node (ref "J3") (pin "1") (pinfunction "1_1") (pintype "power_in"))
      (node (ref "J4") (pin "G1") (pinfunction "GND_1_G1") (pintype "bidirectional"))
      (node (ref "J4") (pin "G2") (pinfunction "GND_2_G2") (pintype "bidirectional"))
      (node (ref "J4") (pin "G3") (pinfunction "GND_3_G3") (pintype "bidirectional"))
      (node (ref "J4") (pin "G4") (pinfunction "GND_4_G4") (pintype "bidirectional"))
      (node (ref "J4") (pin "P6") (pinfunction "VSS_P6") (pintype "bidirectional"))
      (node (ref "MCP73831") (pin "2") (pinfunction "VSS_2") (pintype "power_in"))
      (node (ref "R1_PWRUSB") (pin "1") (pinfunction "1_1") (pintype "passive"))
      (node (ref "R2") (pin "1") (pinfunction "1_1") (pintype "passive"))
      (node (ref "R2-USB") (pin "2") (pinfunction "2_2") (pintype "passive"))
      (node (ref "R2-USB1") (pin "1") (pinfunction "1_1") (pintype "passive"))
      (node (ref "R2_BAT") (pin "1") (pinfunction "1_1") (pintype "passive"))
      (node (ref "R4") (pin "1") (pinfunction "1_1") (pintype "passive"))
      (node (ref "RESET_BUTTON") (pin "1") (pinfunction "1_1") (pintype "passive"))
      (node (ref "RESET_BUTTON") (pin "2") (pinfunction "2_2") (pintype "passive"))
      (node (ref "SENSOR2") (pin "1") (pinfunction "GND_1") (pintype "power_in"))
      (node (ref "SENSOR2") (pin "5") (pinfunction "SDO_5") (pintype "bidirectional"))
      (node (ref "SENSOR2") (pin "7") (pinfunction "GND_7") (pintype "power_in"))
      (node (ref "SJ1") (pin "1") (pinfunction "1_1") (pintype "passive"))
      (node (ref "TP4") (pin "TP") (pinfunction "TP_TP") (pintype "input"))
      (node (ref "TP5") (pin "TP") (pinfunction "TP_TP") (pintype "input"))
      (node (ref "U1") (pin "4") (pinfunction "GND_4") (pintype "power_in"))
      (node (ref "U1") (pin "9") (pinfunction "EXP_9") (pintype "passive"))
      (node (ref "U2") (pin "1") (pinfunction "GND_1") (pintype "power_in"))
      (node (ref "U2") (pin "28") (pinfunction "GND_28") (pintype "power_in"))
      (node (ref "U2") (pin "29_1") (pinfunction "GND_29_1") (pintype "power_in"))
      (node (ref "U2") (pin "29_2") (pinfunction "GND_29_2") (pintype "power_in"))
      (node (ref "U2") (pin "29_3") (pinfunction "GND_29_3") (pintype "power_in"))
      (node (ref "U2") (pin "29_4") (pinfunction "GND_29_4") (pintype "power_in"))
      (node (ref "U2") (pin "29_5") (pinfunction "GND_29_5") (pintype "power_in"))
      (node (ref "U2") (pin "29_6") (pinfunction "GND_29_6") (pintype "power_in"))
      (node (ref "U2") (pin "29_7") (pinfunction "GND_29_7") (pintype "power_in"))
      (node (ref "U2") (pin "29_8") (pinfunction "GND_29_8") (pintype "power_in"))
      (node (ref "U2") (pin "29_9") (pinfunction "GND_29_9") (pintype "power_in"))
      (node (ref "U3") (pin "13") (pinfunction "GND_13") (pintype "power_in"))
      (node (ref "U4") (pin "1") (pinfunction "CTG_1") (pintype "power_in"))
      (node (ref "U4") (pin "4") (pinfunction "GND_4") (pintype "power_in"))
      (node (ref "U4") (pin "6") (pinfunction "QSTRT_6") (pintype "input"))
      (node (ref "U4") (pin "9") (pinfunction "EP_9") (pintype "power_in"))
    )
    (net (code "14") (name "GPIO8") (class "Default")
      (node (ref "R1") (pin "1") (pinfunction "1_1") (pintype "passive"))
      (node (ref "U2") (pin "10") (pinfunction "IO8_10") (pintype "bidirectional"))
    )
    (net (code "15") (name "I2C_PW") (class "Default")
      (node (ref "C1") (pin "1") (pinfunction "1_1") (pintype "passive"))
      (node (ref "C2") (pin "1") (pinfunction "1_1") (pintype "passive"))
      (node (ref "R1_PINH") (pin "2") (pinfunction "2_2") (pintype "passive"))
      (node (ref "R2-PINH") (pin "2") (pinfunction "2_2") (pintype "passive"))
      (node (ref "SENSOR2") (pin "2") (pinfunction "CSB_2") (pintype "input"))
      (node (ref "SENSOR2") (pin "6") (pinfunction "VDDIO_6") (pintype "power_in"))
      (node (ref "SENSOR2") (pin "8") (pinfunction "VDD_8") (pintype "power_in"))
      (node (ref "U2") (pin "17") (pinfunction "IO19_17") (pintype "bidirectional"))
    )
    (net (code "16") (name "INT_RTC") (class "Default")
      (node (ref "R1_PINH1") (pin "1") (pinfunction "1_1") (pintype "passive"))
      (node (ref "TP15") (pin "TP") (pinfunction "TP_TP") (pintype "input"))
      (node (ref "U2") (pin "8") (pinfunction "IO0_8") (pintype "bidirectional"))
      (node (ref "U3") (pin "3") (pinfunction "SQW/~{INT}_3") (pintype "output"))
    )
    (net (code "17") (name "IO{slash}BOOT") (class "Default")
      (node (ref "BOOT_BUTTON") (pin "3") (pinfunction "3_3") (pintype "passive"))
      (node (ref "BOOT_BUTTON") (pin "4") (pinfunction "4_4") (pintype "passive"))
      (node (ref "C6") (pin "1") (pinfunction "1_1") (pintype "passive"))
      (node (ref "R_BOOT") (pin "1") (pinfunction "1_1") (pintype "passive"))
      (node (ref "U2") (pin "15") (pinfunction "IO9_15") (pintype "bidirectional"))
    )
    (net (code "18") (name "IO{slash}CHANGE") (class "Default")
      (node (ref "C10") (pin "1") (pinfunction "1_1") (pintype "passive"))
      (node (ref "CHANGE_BUTTON") (pin "3") (pinfunction "3_3") (pintype "passive"))
      (node (ref "CHANGE_BUTTON") (pin "4") (pinfunction "4_4") (pintype "passive"))
      (node (ref "R_CHANGE") (pin "1") (pinfunction "1_1") (pintype "passive"))
      (node (ref "U2") (pin "23") (pinfunction "IO15_23") (pintype "bidirectional"))
    )
    (net (code "19") (name "MISO") (class "Default")
      (node (ref "D12") (pin "2") (pinfunction "2_2") (pintype "passive"))
      (node (ref "J4") (pin "P7") (pinfunction "DAT0_P7") (pintype "bidirectional"))
      (node (ref "R8") (pin "1") (pinfunction "1_1") (pintype "passive"))
      (node (ref "TP6") (pin "TP") (pinfunction "TP_TP") (pintype "input"))
      (node (ref "U1") (pin "2") (pinfunction "DO(IO1)_2") (pintype "bidirectional"))
      (node (ref "U2") (pin "27") (pinfunction "IO2_27") (pintype "bidirectional"))
    )
    (net (code "20") (name "MOSI") (class "Default")
      (node (ref "D11") (pin "2") (pinfunction "2_2") (pintype "passive"))
      (node (ref "J1") (pin "14") (pinfunction "14_14") (pintype "bidirectional"))
      (node (ref "J4") (pin "P3") (pinfunction "CMD_P3") (pintype "bidirectional"))
      (node (ref "R7") (pin "1") (pinfunction "1_1") (pintype "passive"))
      (node (ref "TP7") (pin "TP") (pinfunction "TP_TP") (pintype "input"))
      (node (ref "U1") (pin "5") (pinfunction "DI(IO0)_5") (pintype "bidirectional"))
      (node (ref "U2") (pin "7") (pinfunction "IO7_7") (pintype "bidirectional"))
    )
    (net (code "21") (name "Net-(CHG_LED-PadC)") (class "Default")
      (node (ref "CHG_LED") (pin "C") (pinfunction "C_C") (pintype "passive"))
      (node (ref "R1_BAT") (pin "1") (pinfunction "1_1") (pintype "passive"))
    )
    (net (code "22") (name "Net-(D2-CATHODE)") (class "Default")
      (node (ref "C1_BAT1") (pin "1") (pinfunction "1_1") (pintype "passive"))
      (node (ref "D2") (pin "1") (pinfunction "CATHODE_1") (pintype "bidirectional"))
      (node (ref "IC4") (pin "1") (pinfunction "VIN_1") (pintype "bidirectional"))
      (node (ref "IC4") (pin "3") (pinfunction "CE_3") (pintype "bidirectional"))
      (node (ref "Q1") (pin "2") (pinfunction "S_2") (pintype "bidirectional"))
    )
    (net (code "23") (name "Net-(D3-A)") (class "Default")
      (node (ref "C4") (pin "1") (pinfunction "1_1") (pintype "passive"))
      (node (ref "D3") (pin "2") (pinfunction "A_2") (pintype "bidirectional"))
      (node (ref "D4") (pin "1") (pinfunction "K_1") (pintype "bidirectional"))
    )
    (net (code "24") (name "Net-(D7-CATHODE)") (class "Default")
      (node (ref "D7") (pin "1") (pinfunction "CATHODE_1") (pintype "bidirectional"))
      (node (ref "R_CAPACITOR") (pin "1") (pinfunction "1_1") (pintype "passive"))
    )
    (net (code "25") (name "Net-(EPD_C1-Pad2)") (class "Default")
      (node (ref "EPD_C1") (pin "2") (pinfunction "2_2") (pintype "passive"))
      (node (ref "J1") (pin "4") (pinfunction "4_4") (pintype "bidirectional"))
    )
    (net (code "26") (name "Net-(EPD_C2-Pad2)") (class "Default")
      (node (ref "EPD_C2") (pin "2") (pinfunction "2_2") (pintype "passive"))
      (node (ref "J1") (pin "5") (pinfunction "5_5") (pintype "bidirectional"))
    )
    (net (code "27") (name "Net-(EPD_C6-Pad2)") (class "Default")
      (node (ref "EPD_C6") (pin "2") (pinfunction "2_2") (pintype "passive"))
      (node (ref "J1") (pin "18") (pinfunction "18_18") (pintype "bidirectional"))
    )
    (net (code "28") (name "Net-(EPD_C7-Pad2)") (class "Default")
      (node (ref "EPD_C7") (pin "2") (pinfunction "2_2") (pintype "passive"))
      (node (ref "J1") (pin "19") (pinfunction "19_19") (pintype "bidirectional"))
    )
    (net (code "29") (name "Net-(EPD_C8-Pad2)") (class "Default")
      (node (ref "EPD_C8") (pin "2") (pinfunction "2_2") (pintype "passive"))
      (node (ref "J1") (pin "20") (pinfunction "20_20") (pintype "bidirectional"))
    )
    (net (code "30") (name "Net-(EPD_C10-Pad2)") (class "Default")
      (node (ref "EPD_C10") (pin "2") (pinfunction "2_2") (pintype "passive"))
      (node (ref "J1") (pin "22") (pinfunction "22_22") (pintype "bidirectional"))
    )
    (net (code "31") (name "Net-(EPD_C12-Pad2)") (class "Default")
      (node (ref "EPD_C12") (pin "2") (pinfunction "2_2") (pintype "passive"))
      (node (ref "J1") (pin "24") (pinfunction "24_24") (pintype "bidirectional"))
    )
    (net (code "32") (name "Net-(IC1-CT)") (class "Default")
      (node (ref "C_DELAY") (pin "1") (pinfunction "1_1") (pintype "passive"))
      (node (ref "IC1") (pin "5") (pinfunction "CT_5") (pintype "bidirectional"))
    )
    (net (code "33") (name "Net-(J2-PadA5)") (class "Default")
      (node (ref "J2") (pin "A5") (pinfunction "A5_A5") (pintype "bidirectional"))
      (node (ref "R2-USB1") (pin "2") (pinfunction "2_2") (pintype "passive"))
    )
    (net (code "34") (name "Net-(J2-PadB5)") (class "Default")
      (node (ref "J2") (pin "B5") (pinfunction "B5_B5") (pintype "bidirectional"))
      (node (ref "R2-USB") (pin "1") (pinfunction "1_1") (pintype "passive"))
    )
    (net (code "35") (name "Net-(MCP73831-PROG)") (class "Default")
      (node (ref "MCP73831") (pin "5") (pinfunction "PROG_5") (pintype "input"))
      (node (ref "R2_BAT") (pin "2") (pinfunction "2_2") (pintype "passive"))
    )
    (net (code "36") (name "Net-(MCP73831-STAT)") (class "Default")
      (node (ref "MCP73831") (pin "1") (pinfunction "STAT_1") (pintype "output"))
      (node (ref "R1_BAT") (pin "2") (pinfunction "2_2") (pintype "passive"))
    )
    (net (code "37") (name "PREVGH") (class "Default")
      (node (ref "D5") (pin "1") (pinfunction "K_1") (pintype "bidirectional"))
      (node (ref "EPD_C9") (pin "2") (pinfunction "2_2") (pintype "passive"))
      (node (ref "J1") (pin "21") (pinfunction "21_21") (pintype "bidirectional"))
    )
    (net (code "38") (name "PREVGL") (class "Default")
      (node (ref "D4") (pin "2") (pinfunction "A_2") (pintype "bidirectional"))
      (node (ref "EPD_C11") (pin "2") (pinfunction "2_2") (pintype "passive"))
      (node (ref "J1") (pin "23") (pinfunction "23_23") (pintype "bidirectional"))
    )
    (net (code "39") (name "RESE") (class "Default")
      (node (ref "J1") (pin "3") (pinfunction "3_3") (pintype "bidirectional"))
      (node (ref "Q3") (pin "2") (pinfunction "S_2") (pintype "bidirectional"))
      (node (ref "R3") (pin "2") (pinfunction "2_2") (pintype "passive"))
    )
    (net (code "40") (name "RESE'") (class "Default")
      (node (ref "R2") (pin "2") (pinfunction "2_2") (pintype "passive"))
      (node (ref "R3") (pin "1") (pinfunction "1_1") (pintype "passive"))
      (node (ref "SJ1") (pin "2") (pinfunction "2_2") (pintype "passive"))
    )
    (net (code "41") (name "RESET") (class "Default")
      (node (ref "C5") (pin "1") (pinfunction "1_1") (pintype "passive"))
      (node (ref "IC1") (pin "1") (pinfunction "VOUT_1") (pintype "bidirectional"))
      (node (ref "RESET_BUTTON") (pin "3") (pinfunction "3_3") (pintype "passive"))
      (node (ref "RESET_BUTTON") (pin "4") (pinfunction "4_4") (pintype "passive"))
      (node (ref "R_RESET") (pin "1") (pinfunction "1_1") (pintype "passive"))
      (node (ref "U2") (pin "3") (pinfunction "EN_3") (pintype "input"))
    )
    (net (code "42") (name "RTC_RST") (class "Default")
      (node (ref "U2") (pin "16") (pinfunction "IO18_16") (pintype "bidirectional"))
      (node (ref "U3") (pin "4") (pinfunction "~{RST}_4") (pintype "input"))
    )
    (net (code "43") (name "RX") (class "Default")
      (node (ref "TP2") (pin "TP") (pinfunction "TP_TP") (pintype "input"))
      (node (ref "U2") (pin "24") (pinfunction "RXD0/GPIO17_24") (pintype "bidirectional"))
    )
    (net (code "44") (name "SCK") (class "Default")
      (node (ref "D10") (pin "2") (pinfunction "2_2") (pintype "passive"))
      (node (ref "J1") (pin "13") (pinfunction "13_13") (pintype "bidirectional"))
      (node (ref "J4") (pin "P5") (pinfunction "CLK_P5") (pintype "bidirectional"))
      (node (ref "R6") (pin "1") (pinfunction "1_1") (pintype "passive"))
      (node (ref "TP8") (pin "TP") (pinfunction "TP_TP") (pintype "input"))
      (node (ref "U1") (pin "6") (pinfunction "CLK_6") (pintype "input"))
      (node (ref "U2") (pin "6") (pinfunction "IO6_6") (pintype "bidirectional"))
    )
    (net (code "45") (name "SCL") (class "Default")
      (node (ref "J3") (pin "4") (pinfunction "4_4") (pintype "passive"))
      (node (ref "R2-PINH") (pin "1") (pinfunction "1_1") (pintype "passive"))
      (node (ref "SENSOR2") (pin "4") (pinfunction "SCK_4") (pintype "input"))
      (node (ref "U2") (pin "20") (pinfunction "IO22_20") (pintype "bidirectional"))
      (node (ref "U3") (pin "16") (pinfunction "SCL_16") (pintype "input"))
      (node (ref "U4") (pin "7") (pinfunction "SCL_7") (pintype "input"))
    )
    (net (code "46") (name "SDA") (class "Default")
      (node (ref "J3") (pin "3") (pinfunction "3_3") (pintype "passive"))
      (node (ref "R1_PINH") (pin "1") (pinfunction "1_1") (pintype "passive"))
      (node (ref "SENSOR2") (pin "3") (pinfunction "SDI_3") (pintype "bidirectional"))
      (node (ref "U2") (pin "19") (pinfunction "IO21_19") (pintype "bidirectional"))
      (node (ref "U3") (pin "15") (pinfunction "SDA_15") (pintype "bidirectional"))
      (node (ref "U4") (pin "8") (pinfunction "SDA_8") (pintype "bidirectional"))
    )
    (net (code "47") (name "SRC") (class "Default")
      (node (ref "C4") (pin "2") (pinfunction "2_2") (pintype "passive"))
      (node (ref "D5") (pin "2") (pinfunction "A_2") (pintype "bidirectional"))
      (node (ref "L1") (pin "1") (pinfunction "1_1") (pintype "passive"))
      (node (ref "Q3") (pin "3") (pinfunction "D_3") (pintype "bidirectional"))
    )
    (net (code "48") (name "SS_SD") (class "Default")
      (node (ref "D8") (pin "2") (pinfunction "2_2") (pintype "passive"))
      (node (ref "J4") (pin "P2") (pinfunction "CD/DAT3_P2") (pintype "bidirectional"))
      (node (ref "R10") (pin "1") (pinfunction "1_1") (pintype "passive"))
      (node (ref "U2") (pin "4") (pinfunction "IO4_4") (pintype "bidirectional"))
    )
    (net (code "49") (name "TX") (class "Default")
      (node (ref "TP1") (pin "TP") (pinfunction "TP_TP") (pintype "input"))
      (node (ref "U2") (pin "25") (pinfunction "TXD0/GPIO16_25") (pintype "bidirectional"))
    )
    (net (code "50") (name "USB_D+") (class "Default")
      (node (ref "D1") (pin "1") (pinfunction "I/O1_1_1") (pintype "bidirectional"))
      (node (ref "U2") (pin "14") (pinfunction "IO13_14") (pintype "bidirectional"))
    )
    (net (code "51") (name "USB_D-") (class "Default")
      (node (ref "D1") (pin "3") (pinfunction "I/O2_1_3") (pintype "bidirectional"))
      (node (ref "U2") (pin "13") (pinfunction "IO12_13") (pintype "bidirectional"))
    )
    (net (code "52") (name "VBAT") (class "Default")
      (node (ref "C2_BAT") (pin "1") (pinfunction "1_1") (pintype "passive"))
      (node (ref "MCP73831") (pin "3") (pinfunction "VBAT_3") (pintype "power_in"))
      (node (ref "Q1") (pin "3") (pinfunction "D_3") (pintype "bidirectional"))
      (node (ref "TP3") (pin "TP") (pinfunction "TP_TP") (pintype "input"))
      (node (ref "U4") (pin "2") (pinfunction "CELL_2") (pintype "power_in"))
      (node (ref "U4") (pin "3") (pinfunction "VDD_3") (pintype "power_in"))
    )
    (net (code "53") (name "VBUS") (class "Default")
      (node (ref "C1_BAT") (pin "1") (pinfunction "1_1") (pintype "passive"))
      (node (ref "C4_USB") (pin "1") (pinfunction "1_1") (pintype "passive"))
      (node (ref "C5_USB") (pin "1") (pinfunction "1_1") (pintype "passive"))
      (node (ref "CHG_LED") (pin "A") (pinfunction "A_A") (pintype "passive"))
      (node (ref "D1") (pin "5") (pinfunction "VBUS_5") (pintype "bidirectional"))
      (node (ref "D2") (pin "2") (pinfunction "ANODE_2") (pintype "bidirectional"))
      (node (ref "MCP73831") (pin "4") (pinfunction "VIN_4") (pintype "power_in"))
      (node (ref "PFMF.050.1") (pin "2") (pinfunction "2_2") (pintype "passive"))
      (node (ref "Q1") (pin "1") (pinfunction "G_1") (pintype "bidirectional"))
      (node (ref "R1_PWRUSB") (pin "2") (pinfunction "2_2") (pintype "passive"))
      (node (ref "TP14") (pin "TP") (pinfunction "TP_TP") (pintype "input"))
    )
    (net (code "54") (name "VRTC") (class "Default")
      (node (ref "C10_SUPERCAP") (pin "2") (pinfunction "2_2") (pintype "passive"))
      (node (ref "C8") (pin "1") (pinfunction "1_1") (pintype "passive"))
      (node (ref "R_CAPACITOR") (pin "2") (pinfunction "2_2") (pintype "passive"))
      (node (ref "U3") (pin "14") (pinfunction "VBAT_14") (pintype "power_in"))
    )
    (net (code "55") (name "VUSB") (class "Default")
      (node (ref "J2") (pin "A4") (pinfunction "A4_A4") (pintype "bidirectional"))
      (node (ref "J2") (pin "A9") (pinfunction "A9_A9") (pintype "bidirectional"))
      (node (ref "J2") (pin "B4") (pinfunction "B4_B4") (pintype "bidirectional"))
      (node (ref "J2") (pin "B9") (pinfunction "B9_B9") (pintype "bidirectional"))
      (node (ref "PFMF.050.1") (pin "1") (pinfunction "1_1") (pintype "passive"))
    )
    (net (code "56") (name "unconnected-(IC1-NC-Pad4)") (class "Default")
      (node (ref "IC1") (pin "4") (pinfunction "NC_4") (pintype "no_connect"))
    )
    (net (code "57") (name "unconnected-(IC4-NC-Pad4)") (class "Default")
      (node (ref "IC4") (pin "4") (pinfunction "NC_4") (pintype "no_connect"))
    )
    (net (code "58") (name "unconnected-(J1-Pad1)") (class "Default")
      (node (ref "J1") (pin "1") (pinfunction "1_1") (pintype "bidirectional"))
    )
    (net (code "59") (name "unconnected-(J1-Pad6)") (class "Default")
      (node (ref "J1") (pin "6") (pinfunction "6_6") (pintype "bidirectional"))
    )
    (net (code "60") (name "unconnected-(J1-Pad7)") (class "Default")
      (node (ref "J1") (pin "7") (pinfunction "7_7") (pintype "bidirectional"))
    )
    (net (code "61") (name "unconnected-(J2-PadA8)") (class "Default")
      (node (ref "J2") (pin "A8") (pinfunction "A8_A8") (pintype "bidirectional"))
    )
    (net (code "62") (name "unconnected-(J2-PadB8)") (class "Default")
      (node (ref "J2") (pin "B8") (pinfunction "B8_B8") (pintype "bidirectional"))
    )
    (net (code "63") (name "unconnected-(J4-DAT1-PadP8)") (class "Default")
      (node (ref "J4") (pin "P8") (pinfunction "DAT1_P8") (pintype "bidirectional"))
    )
    (net (code "64") (name "unconnected-(J4-DAT2-PadP1)") (class "Default")
      (node (ref "J4") (pin "P1") (pinfunction "DAT2_P1") (pintype "bidirectional"))
    )
    (net (code "65") (name "unconnected-(J4-DETECTION_1-PadS1)") (class "Default")
      (node (ref "J4") (pin "S1") (pinfunction "DETECTION_1_S1") (pintype "bidirectional"))
    )
    (net (code "66") (name "unconnected-(J4-DETECTION_2-PadS2)") (class "Default")
      (node (ref "J4") (pin "S2") (pinfunction "DETECTION_2_S2") (pintype "bidirectional"))
    )
    (net (code "67") (name "unconnected-(U2-NC-Pad22)") (class "Default")
      (node (ref "U2") (pin "22") (pinfunction "NC_22") (pintype "no_connect"))
    )
    (net (code "68") (name "unconnected-(U4-~{ALERT}-Pad5)") (class "Default")
      (node (ref "U4") (pin "5") (pinfunction "~{ALERT}_5") (pintype "output"))
    )
  )
)
